# top_blank.net
KiCad netlist of a schematic drawn in Altium Designer
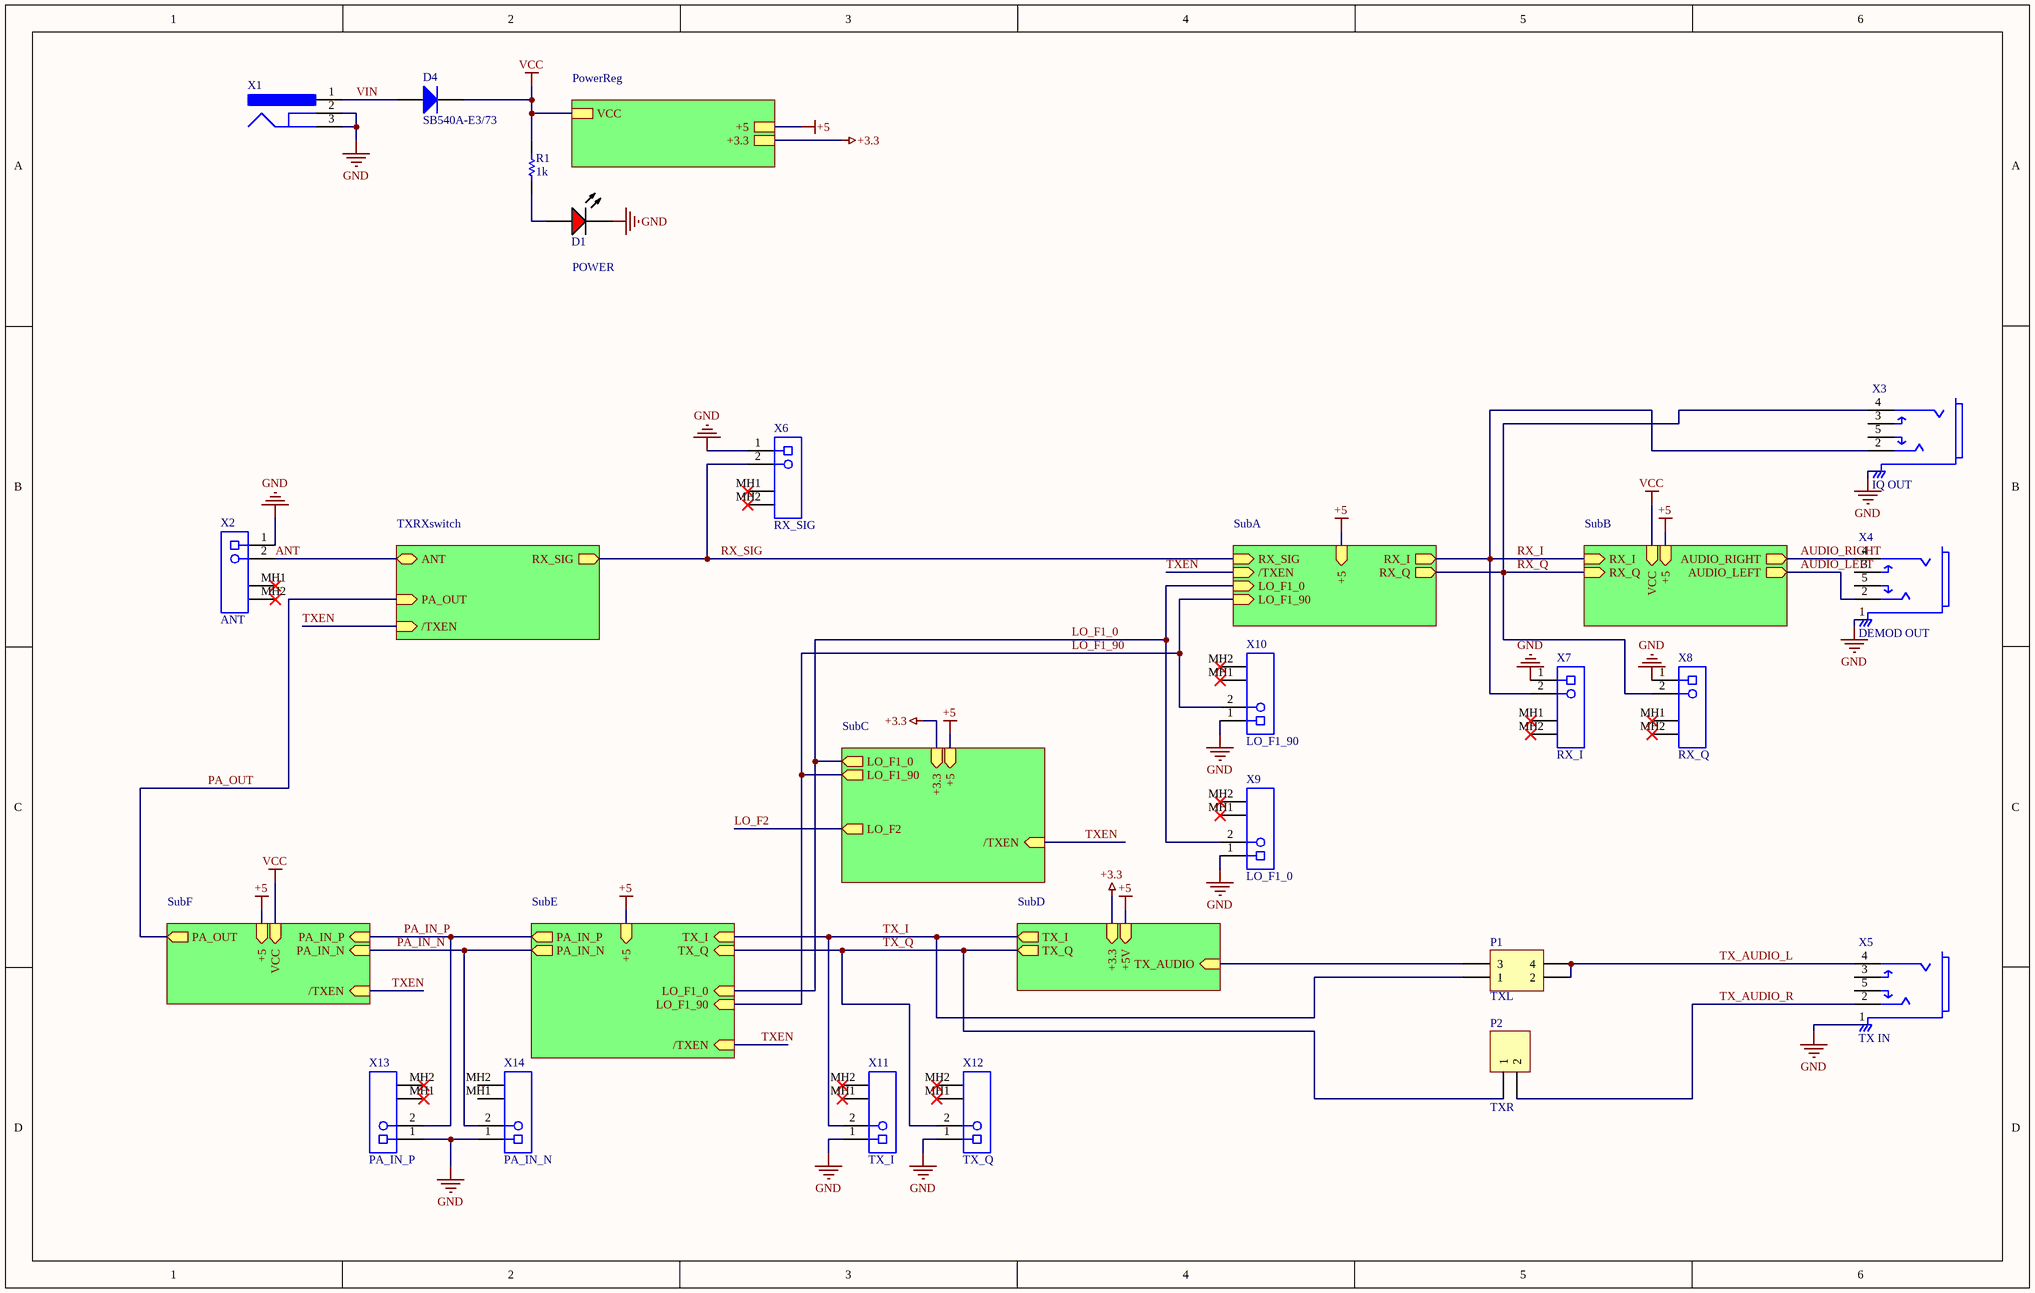
[diagram p0: top_blank.SchDoc]

(export (version "E")
  (design (tool "Eeschema 10.0.6"))
  (components
    (comp (ref "D1")
      (value "POWER")
      (footprint "AVAG-HLMP-3301-2")
      (description "T-1 3/4 (5 mm) Diffused LED Lamp, 1.9 V, -40 to 100 degC, 2-Pin THD, RoHS, Bulk")
      (fields (field (name "MANUFACTURER") "Avago"))
      (libsource (lib "Altium Content Vault") (part "LED-RED-K1A2-2"))
    )
    (comp (ref "D4")
      (value "SB540A-E3/73")
      (footprint "DO-201AD")
      (description "3 Amp Medium Power Silicon Rectifier Diode")
      (fields (field (name "PUBLISHER") "Altium Limited"))
      (libsource (lib "Miscellaneous Devices") (part "Diode 1N5408"))
    )
    (comp (ref "P1")
      (value "TXL")
      (footprint "HDR2X2")
      (description "Header, 2-Pin, Dual row")
      (fields (field (name "PUBLISHER") "Altium Limited"))
      (libsource (lib "Miscellaneous Connectors") (part "Header 2X2"))
    )
    (comp (ref "P2")
      (value "TXR")
      (footprint "HDR1X2")
      (description "Header, 2-Pin")
      (fields (field (name "PUBLISHER") "Altium Limited"))
      (libsource (lib "Miscellaneous Connectors") (part "Header 2"))
    )
    (comp (ref "R1")
      (value "1k")
      (footprint "AXIAL-0.4")
      (description "Resistor")
      (fields (field (name "Comment") "Res1") (field (name "PUBLISHER") "Altium Limited"))
      (libsource (lib "Miscellaneous Devices") (part "Res1"))
    )
    (comp (ref "X1")
      (value "PJ-002A")
      (footprint "CUI-PJ-002A_V")
      (fields (field (name "MANUFACTURER") "CUIInc."))
      (libsource (lib "Altium Content Vault") (part "JACK-2CD3-RN"))
    )
    (comp (ref "X2")
      (value "ANT")
      (footprint "TECO-1-1337543-0_V")
      (fields (field (name "MANUFACTURER") "TE Connectivity"))
      (libsource (lib "Altium Content Vault") (part "CN-1P-F-R2_A"))
    )
    (comp (ref "X3")
      (value "IQ OUT")
      (footprint "FP-35RAPC4BV4-MFG")
      (description "CONN JACK STEREO 3.5MM R/A")
      (fields (field (name "MANUFACTURER") "Switchcraft") (field (name "OBSOLETE PART") "true"))
      (libsource (lib "Altium Content Vault") (part "75ff47c9dea01840d0d9527457fc737"))
    )
    (comp (ref "X4")
      (value "DEMOD OUT")
      (footprint "FP-35RAPC4BV4-MFG")
      (description "CONN JACK STEREO 3.5MM R/A")
      (fields (field (name "MANUFACTURER") "Switchcraft") (field (name "OBSOLETE PART") "true"))
      (libsource (lib "Altium Content Vault") (part "75ff47c9dea01840d0d9527457fc737"))
    )
    (comp (ref "X5")
      (value "TX IN")
      (footprint "FP-35RAPC4BV4-MFG")
      (description "CONN JACK STEREO 3.5MM R/A")
      (fields (field (name "MANUFACTURER") "Switchcraft") (field (name "OBSOLETE PART") "true"))
      (libsource (lib "Altium Content Vault") (part "75ff47c9dea01840d0d9527457fc737"))
    )
    (comp (ref "X6")
      (value "RX_SIG")
      (footprint "TECO-1-1337543-0_V")
      (fields (field (name "MANUFACTURER") "TE Connectivity"))
      (libsource (lib "") (part "CN-1P-F-R2_A_3"))
    )
    (comp (ref "X7")
      (value "RX_I")
      (footprint "TECO-1-1337543-0_V")
      (fields (field (name "MANUFACTURER") "TE Connectivity"))
      (libsource (lib "") (part "CN-1P-F-R2_A_3"))
    )
    (comp (ref "X8")
      (value "RX_Q")
      (footprint "TECO-1-1337543-0_V")
      (fields (field (name "MANUFACTURER") "TE Connectivity"))
      (libsource (lib "") (part "CN-1P-F-R2_A_3"))
    )
    (comp (ref "X9")
      (value "LO_F1_0")
      (footprint "TECO-1-1337543-0_V")
      (fields (field (name "MANUFACTURER") "TE Connectivity"))
      (libsource (lib "") (part "CN-1P-F-R2_A_2"))
    )
    (comp (ref "X10")
      (value "LO_F1_90")
      (footprint "TECO-1-1337543-0_V")
      (fields (field (name "MANUFACTURER") "TE Connectivity"))
      (libsource (lib "") (part "CN-1P-F-R2_A_2"))
    )
    (comp (ref "X11")
      (value "TX_I")
      (footprint "TECO-1-1337543-0_V")
      (fields (field (name "MANUFACTURER") "TE Connectivity"))
      (libsource (lib "") (part "CN-1P-F-R2_A_2"))
    )
    (comp (ref "X12")
      (value "TX_Q")
      (footprint "TECO-1-1337543-0_V")
      (fields (field (name "MANUFACTURER") "TE Connectivity"))
      (libsource (lib "") (part "CN-1P-F-R2_A_2"))
    )
    (comp (ref "X13")
      (value "PA_IN_P")
      (footprint "TECO-1-1337543-0_V")
      (fields (field (name "MANUFACTURER") "TE Connectivity"))
      (libsource (lib "") (part "CN-1P-F-R2_A_1"))
    )
    (comp (ref "X14")
      (value "PA_IN_N")
      (footprint "TECO-1-1337543-0_V")
      (fields (field (name "MANUFACTURER") "TE Connectivity"))
      (libsource (lib "") (part "CN-1P-F-R2_A_2"))
    )
  )
  (nets
    (net (code "3") (name "/ANT") (class "Default")
      (node (ref "X2") (pin "2") (pinfunction "2_2") (pintype "passive"))
    )
    (net (code "4") (name "/AUDIO_LEFT") (class "Default")
      (node (ref "X4") (pin "2") (pinfunction "2_2") (pintype "passive"))
    )
    (net (code "5") (name "/AUDIO_RIGHT") (class "Default")
      (node (ref "X4") (pin "4") (pinfunction "4_4") (pintype "passive"))
    )
    (net (code "6") (name "/LO_F1_0") (class "Default")
      (node (ref "X9") (pin "2") (pinfunction "2_2") (pintype "passive"))
    )
    (net (code "7") (name "/LO_F1_90") (class "Default")
      (node (ref "X10") (pin "2") (pinfunction "2_2") (pintype "passive"))
    )
    (net (code "9") (name "/PA_IN_N") (class "Default")
      (node (ref "X14") (pin "2") (pinfunction "2_2") (pintype "passive"))
    )
    (net (code "10") (name "/PA_IN_P") (class "Default")
      (node (ref "X13") (pin "2") (pinfunction "2_2") (pintype "passive"))
    )
    (net (code "12") (name "/RX_I") (class "Default")
      (node (ref "X3") (pin "2") (pinfunction "2_2") (pintype "passive"))
      (node (ref "X7") (pin "2") (pinfunction "2_2") (pintype "passive"))
    )
    (net (code "13") (name "/RX_Q") (class "Default")
      (node (ref "X3") (pin "4") (pinfunction "4_4") (pintype "passive"))
      (node (ref "X8") (pin "2") (pinfunction "2_2") (pintype "passive"))
    )
    (net (code "14") (name "/RX_SIG") (class "Default")
      (node (ref "X6") (pin "2") (pinfunction "2_2") (pintype "passive"))
    )
    (net (code "16") (name "/TX_AUDIO") (class "Default")
      (node (ref "P1") (pin "3") (pinfunction "3_3") (pintype "passive"))
    )
    (net (code "17") (name "/TX_AUDIO_L") (class "Default")
      (node (ref "P1") (pin "2") (pinfunction "2_2") (pintype "passive"))
      (node (ref "P1") (pin "4") (pinfunction "4_4") (pintype "passive"))
      (node (ref "X5") (pin "4") (pinfunction "4_4") (pintype "passive"))
    )
    (net (code "18") (name "/TX_AUDIO_R") (class "Default")
      (node (ref "P2") (pin "2") (pinfunction "2_2") (pintype "passive"))
      (node (ref "X5") (pin "2") (pinfunction "2_2") (pintype "passive"))
    )
    (net (code "19") (name "/TX_I") (class "Default")
      (node (ref "P1") (pin "1") (pinfunction "1_1") (pintype "passive"))
      (node (ref "X11") (pin "2") (pinfunction "2_2") (pintype "passive"))
    )
    (net (code "20") (name "/TX_Q") (class "Default")
      (node (ref "P2") (pin "1") (pinfunction "1_1") (pintype "passive"))
      (node (ref "X12") (pin "2") (pinfunction "2_2") (pintype "passive"))
    )
    (net (code "21") (name "/VIN") (class "Default")
      (node (ref "D4") (pin "1") (pinfunction "A_1") (pintype "passive"))
      (node (ref "X1") (pin "1") (pinfunction "1_1") (pintype "passive"))
    )
    (net (code "22") (name "GND") (class "Default")
      (node (ref "D1") (pin "1") (pinfunction "K_1") (pintype "passive"))
      (node (ref "X1") (pin "2") (pinfunction "2_2") (pintype "passive"))
      (node (ref "X1") (pin "3") (pinfunction "3_3") (pintype "passive"))
      (node (ref "X10") (pin "1") (pinfunction "1_1") (pintype "passive"))
      (node (ref "X11") (pin "1") (pinfunction "1_1") (pintype "passive"))
      (node (ref "X12") (pin "1") (pinfunction "1_1") (pintype "passive"))
      (node (ref "X13") (pin "1") (pinfunction "1_1") (pintype "passive"))
      (node (ref "X14") (pin "1") (pinfunction "1_1") (pintype "passive"))
      (node (ref "X2") (pin "1") (pinfunction "1_1") (pintype "passive"))
      (node (ref "X3") (pin "1") (pinfunction "1_1") (pintype "passive"))
      (node (ref "X4") (pin "1") (pinfunction "1_1") (pintype "passive"))
      (node (ref "X5") (pin "1") (pinfunction "1_1") (pintype "passive"))
      (node (ref "X6") (pin "1") (pinfunction "1_1") (pintype "passive"))
      (node (ref "X7") (pin "1") (pinfunction "1_1") (pintype "passive"))
      (node (ref "X8") (pin "1") (pinfunction "1_1") (pintype "passive"))
      (node (ref "X9") (pin "1") (pinfunction "1_1") (pintype "passive"))
    )
    (net (code "23") (name "Net-(D1-A)") (class "Default")
      (node (ref "D1") (pin "2") (pinfunction "A_2") (pintype "passive"))
      (node (ref "R1") (pin "1") (pinfunction "1_1") (pintype "passive"))
    )
    (net (code "24") (name "VCC") (class "Default")
      (node (ref "D4") (pin "2") (pinfunction "K_2") (pintype "passive"))
      (node (ref "R1") (pin "2") (pinfunction "2_2") (pintype "passive"))
    )
    (net (code "25") (name "unconnected-(X2-PadMH1)") (class "Default")
      (node (ref "X2") (pin "MH1") (pinfunction "MH1_MH1") (pintype "passive+no_connect"))
    )
    (net (code "26") (name "unconnected-(X2-PadMH2)") (class "Default")
      (node (ref "X2") (pin "MH2") (pinfunction "MH2_MH2") (pintype "passive+no_connect"))
    )
    (net (code "27") (name "unconnected-(X3-Pad3)") (class "Default")
      (node (ref "X3") (pin "3") (pinfunction "3_3") (pintype "passive"))
    )
    (net (code "28") (name "unconnected-(X3-Pad5)") (class "Default")
      (node (ref "X3") (pin "5") (pinfunction "5_5") (pintype "passive"))
    )
    (net (code "29") (name "unconnected-(X4-Pad3)") (class "Default")
      (node (ref "X4") (pin "3") (pinfunction "3_3") (pintype "passive"))
    )
    (net (code "30") (name "unconnected-(X4-Pad5)") (class "Default")
      (node (ref "X4") (pin "5") (pinfunction "5_5") (pintype "passive"))
    )
    (net (code "31") (name "unconnected-(X5-Pad3)") (class "Default")
      (node (ref "X5") (pin "3") (pinfunction "3_3") (pintype "passive"))
    )
    (net (code "32") (name "unconnected-(X5-Pad5)") (class "Default")
      (node (ref "X5") (pin "5") (pinfunction "5_5") (pintype "passive"))
    )
    (net (code "33") (name "unconnected-(X6-PadMH1)") (class "Default")
      (node (ref "X6") (pin "MH1") (pinfunction "MH1_MH1") (pintype "passive+no_connect"))
    )
    (net (code "34") (name "unconnected-(X6-PadMH2)") (class "Default")
      (node (ref "X6") (pin "MH2") (pinfunction "MH2_MH2") (pintype "passive+no_connect"))
    )
    (net (code "35") (name "unconnected-(X7-PadMH1)") (class "Default")
      (node (ref "X7") (pin "MH1") (pinfunction "MH1_MH1") (pintype "passive+no_connect"))
    )
    (net (code "36") (name "unconnected-(X7-PadMH2)") (class "Default")
      (node (ref "X7") (pin "MH2") (pinfunction "MH2_MH2") (pintype "passive+no_connect"))
    )
    (net (code "37") (name "unconnected-(X8-PadMH1)") (class "Default")
      (node (ref "X8") (pin "MH1") (pinfunction "MH1_MH1") (pintype "passive+no_connect"))
    )
    (net (code "38") (name "unconnected-(X8-PadMH2)") (class "Default")
      (node (ref "X8") (pin "MH2") (pinfunction "MH2_MH2") (pintype "passive+no_connect"))
    )
    (net (code "39") (name "unconnected-(X9-PadMH1)") (class "Default")
      (node (ref "X9") (pin "MH1") (pinfunction "MH1_MH1") (pintype "passive+no_connect"))
    )
    (net (code "40") (name "unconnected-(X9-PadMH2)") (class "Default")
      (node (ref "X9") (pin "MH2") (pinfunction "MH2_MH2") (pintype "passive+no_connect"))
    )
    (net (code "41") (name "unconnected-(X10-PadMH1)") (class "Default")
      (node (ref "X10") (pin "MH1") (pinfunction "MH1_MH1") (pintype "passive+no_connect"))
    )
    (net (code "42") (name "unconnected-(X10-PadMH2)") (class "Default")
      (node (ref "X10") (pin "MH2") (pinfunction "MH2_MH2") (pintype "passive+no_connect"))
    )
    (net (code "43") (name "unconnected-(X11-PadMH1)") (class "Default")
      (node (ref "X11") (pin "MH1") (pinfunction "MH1_MH1") (pintype "passive+no_connect"))
    )
    (net (code "44") (name "unconnected-(X11-PadMH2)") (class "Default")
      (node (ref "X11") (pin "MH2") (pinfunction "MH2_MH2") (pintype "passive+no_connect"))
    )
    (net (code "45") (name "unconnected-(X12-PadMH1)") (class "Default")
      (node (ref "X12") (pin "MH1") (pinfunction "MH1_MH1") (pintype "passive+no_connect"))
    )
    (net (code "46") (name "unconnected-(X12-PadMH2)") (class "Default")
      (node (ref "X12") (pin "MH2") (pinfunction "MH2_MH2") (pintype "passive+no_connect"))
    )
    (net (code "47") (name "unconnected-(X13-PadMH1)") (class "Default")
      (node (ref "X13") (pin "MH1") (pinfunction "MH1_MH1") (pintype "passive+no_connect"))
    )
    (net (code "48") (name "unconnected-(X13-PadMH2)") (class "Default")
      (node (ref "X13") (pin "MH2") (pinfunction "MH2_MH2") (pintype "passive+no_connect"))
    )
    (net (code "49") (name "unconnected-(X14-PadMH1)") (class "Default")
      (node (ref "X14") (pin "MH1") (pinfunction "MH1_MH1") (pintype "passive"))
    )
    (net (code "50") (name "unconnected-(X14-PadMH2)") (class "Default")
      (node (ref "X14") (pin "MH2") (pinfunction "MH2_MH2") (pintype "passive"))
    )
  )
)
